# CPU.net
KiCad netlist of a schematic drawn in Altium Designer
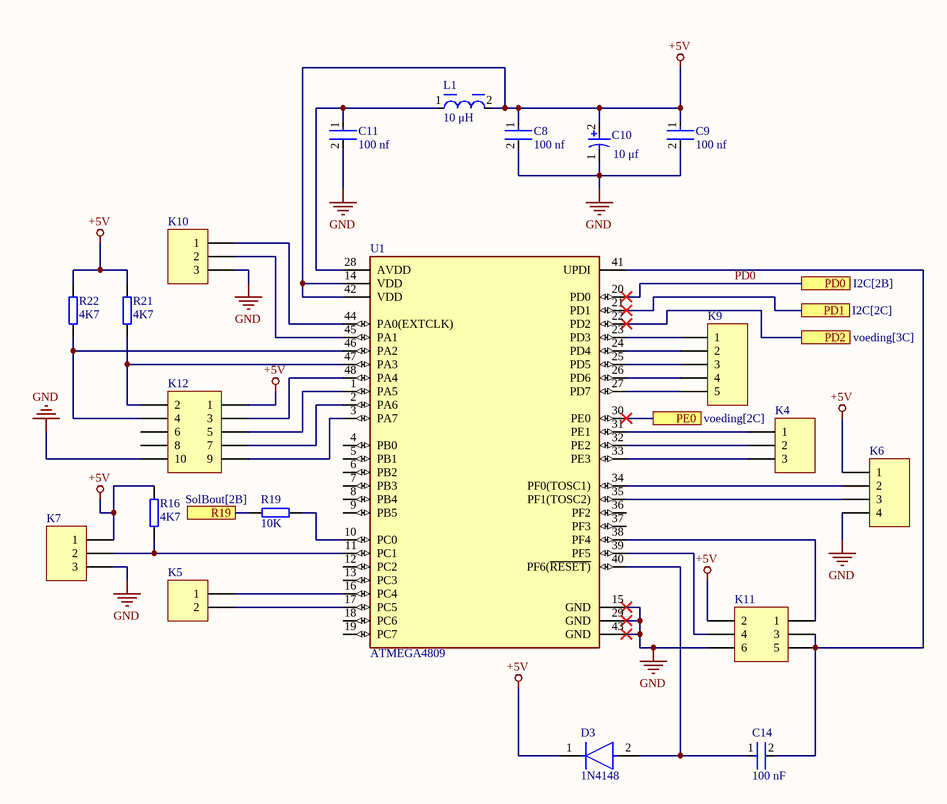
[diagram p0: CPU.SchDoc]

(export (version "E")
  (design (tool "Eeschema 10.0.6"))
  (components
    (comp (ref "C8")
      (value "100 nf")
      (footprint "CC_0805_L")
      (fields
        (field (name "MANUFACTURER") "KEMET")
        (field (name "OCTOPART") "https://octopart.com/c0805c224k5ractu-kemet-144670")
        (field (name "MANUFACTURER PART NUMBER") "C0805C224K5RACTU")
      )
      (libsource (lib "Soldeerstation_Final") (part "Capacitor_Ceramic"))
    )
    (comp (ref "C9")
      (value "100 nf")
      (footprint "CC_0805_L")
      (fields
        (field (name "MANUFACTURER") "KEMET")
        (field (name "OCTOPART") "https://octopart.com/c0805c224k5ractu-kemet-144670")
        (field (name "MANUFACTURER PART NUMBER") "C0805C224K5RACTU")
      )
      (libsource (lib "Soldeerstation_Final") (part "Capacitor_Ceramic"))
    )
    (comp (ref "C10")
      (value "10 μf")
      (footprint "CE_D8_L10")
      (fields (field (name "MANUFACTURER") "Panasonic"))
      (libsource (lib "Soldeerstation_Final") (part "Capacitor_Electrolytic"))
    )
    (comp (ref "C11")
      (value "100 nf")
      (footprint "CC_0805_L")
      (fields
        (field (name "MANUFACTURER") "KEMET")
        (field (name "OCTOPART") "https://octopart.com/c0805c224k5ractu-kemet-144670")
        (field (name "MANUFACTURER PART NUMBER") "C0805C224K5RACTU")
      )
      (libsource (lib "Soldeerstation_Final") (part "Capacitor_Ceramic"))
    )
    (comp (ref "C14")
      (value "100 nF")
      (footprint "CC_0805_L")
      (fields
        (field (name "MANUFACTURER") "KEMET")
        (field (name "OCTOPART") "https://octopart.com/c0805c224k5ractu-kemet-144670")
        (field (name "MANUFACTURER PART NUMBER") "C0805C224K5RACTU")
      )
      (libsource (lib "Soldeerstation_Final") (part "Capacitor_Ceramic"))
    )
    (comp (ref "D3")
      (value "1N4148")
      (footprint "SOD-123FL")
      (fields
        (field (name "MANUFACTURER PART NUMBER") "1N4007")
        (field (name "MANUFACTURER") "Diotec")
        (field (name "OCTOPART") "https://octopart.com/1n4007-diotec-4040411")
      )
      (libsource (lib "Soldeerstation_Final") (part "Diode"))
    )
    (comp (ref "K4")
      (value "~")
      (footprint "HDR1X3")
      (description "Header, 3-Pin")
      (fields (field (name "PUBLISHER") "Altium Limited"))
      (libsource (lib "") (part "Header 3_1"))
    )
    (comp (ref "K5")
      (value "~")
      (footprint "HDR1X2")
      (description "Header, 2-Pin")
      (fields (field (name "PUBLISHER") "Altium Limited"))
      (libsource (lib "Miscellaneous Connectors") (part "Header 2"))
    )
    (comp (ref "K6")
      (value "~")
      (footprint "HDR1X4")
      (description "Header, 4-Pin")
      (fields (field (name "PUBLISHER") "Altium Limited"))
      (libsource (lib "Miscellaneous Connectors") (part "Header 4"))
    )
    (comp (ref "K7")
      (value "~")
      (footprint "HDR1X3")
      (description "Header, 3-Pin")
      (fields (field (name "PUBLISHER") "Altium Limited"))
      (libsource (lib "Miscellaneous Connectors") (part "Header 3"))
    )
    (comp (ref "K9")
      (value "~")
      (footprint "HDR1X5")
      (description "Header, 5-Pin")
      (fields (field (name "PUBLISHER") "Altium Limited"))
      (libsource (lib "Miscellaneous Connectors") (part "Header 5"))
    )
    (comp (ref "K10")
      (value "~")
      (footprint "HDR1X3")
      (description "Header, 3-Pin")
      (fields (field (name "PUBLISHER") "Altium Limited"))
      (libsource (lib "Miscellaneous Connectors") (part "Header 3"))
    )
    (comp (ref "K11")
      (value "~")
      (footprint "HDR2X3")
      (description "Header, 3-Pin, Dual row")
      (fields (field (name "PUBLISHER") "Altium Limited"))
      (libsource (lib "Miscellaneous Connectors") (part "Header 3X2"))
    )
    (comp (ref "K12")
      (value "~")
      (footprint "HDR2X5")
      (description "Header, 5-Pin, Dual row")
      (fields (field (name "PUBLISHER") "Altium Limited"))
      (libsource (lib "Miscellaneous Connectors") (part "Header 5X2"))
    )
    (comp (ref "L1")
      (value "10 μH")
      (footprint "CC_0805_L")
      (fields (field (name "TOLERANCE") "20%"))
      (libsource (lib "Soldeerstation_Final") (part "Choke"))
    )
    (comp (ref "R16")
      (value "4K7")
      (footprint "CC_0805_m")
      (fields (field (name "MANUFACTURER") "Vishay Dale") (field (name "PART NUMBER") "CRCW08050000Z0EA"))
      (libsource (lib "Soldeerstation_Final") (part "Resistor"))
    )
    (comp (ref "R19")
      (value "10K")
      (footprint "CC_0805_m")
      (fields (field (name "MANUFACTURER") "Vishay Dale") (field (name "PART NUMBER") "CRCW08050000Z0EA"))
      (libsource (lib "Soldeerstation_Final") (part "Resistor"))
    )
    (comp (ref "R21")
      (value "4K7")
      (footprint "CC_0805_m")
      (fields (field (name "MANUFACTURER") "Vishay Dale") (field (name "PART NUMBER") "CRCW08050000Z0EA"))
      (libsource (lib "Soldeerstation_Final") (part "Resistor"))
    )
    (comp (ref "R22")
      (value "4K7")
      (footprint "CC_0805_m")
      (fields (field (name "MANUFACTURER") "Vishay Dale") (field (name "PART NUMBER") "CRCW08050000Z0EA"))
      (libsource (lib "Soldeerstation_Final") (part "Resistor"))
    )
    (comp (ref "U1")
      (value "ATMEGA4809")
      (footprint "TQFP_48_M")
      (libsource (lib "Soldeerstation_Final") (part "ATMEGA4809"))
    )
  )
  (nets
    (net (code "1") (name "+5V") (class "Default")
      (node (ref "C10") (pin "2") (pinfunction "2_2") (pintype "passive"))
      (node (ref "C8") (pin "1") (pinfunction "1_1") (pintype "passive"))
      (node (ref "C9") (pin "1") (pinfunction "1_1") (pintype "passive"))
      (node (ref "D3") (pin "1") (pinfunction "C_1") (pintype "passive"))
      (node (ref "K11") (pin "2") (pinfunction "2_2") (pintype "passive"))
      (node (ref "K12") (pin "1") (pinfunction "1_1") (pintype "passive"))
      (node (ref "K6") (pin "1") (pinfunction "1_1") (pintype "passive"))
      (node (ref "K7") (pin "1") (pinfunction "1_1") (pintype "passive"))
      (node (ref "L1") (pin "2") (pinfunction "2_2") (pintype "passive"))
      (node (ref "R16") (pin "2") (pinfunction "2_2") (pintype "passive"))
      (node (ref "R21") (pin "2") (pinfunction "2_2") (pintype "passive"))
      (node (ref "R22") (pin "2") (pinfunction "2_2") (pintype "passive"))
      (node (ref "U1") (pin "14") (pinfunction "VDD_14") (pintype "power_in"))
      (node (ref "U1") (pin "42") (pinfunction "VDD_42") (pintype "power_in"))
    )
    (net (code "2") (name "/PD0") (class "Default")
      (node (ref "U1") (pin "20") (pinfunction "PD0_20") (pintype "bidirectional+no_connect"))
    )
    (net (code "3") (name "/PD1") (class "Default")
      (node (ref "U1") (pin "21") (pinfunction "PD1_21") (pintype "bidirectional+no_connect"))
    )
    (net (code "4") (name "/PD2") (class "Default")
      (node (ref "U1") (pin "22") (pinfunction "PD2_22") (pintype "bidirectional+no_connect"))
    )
    (net (code "5") (name "/PE0") (class "Default")
      (node (ref "U1") (pin "30") (pinfunction "PE0_30") (pintype "bidirectional+no_connect"))
    )
    (net (code "6") (name "/R19") (class "Default")
      (node (ref "R19") (pin "1") (pinfunction "1_1") (pintype "passive"))
    )
    (net (code "7") (name "GND") (class "Default")
      (node (ref "C10") (pin "1") (pinfunction "1_1") (pintype "passive"))
      (node (ref "C11") (pin "2") (pinfunction "2_2") (pintype "passive"))
      (node (ref "C8") (pin "2") (pinfunction "2_2") (pintype "passive"))
      (node (ref "C9") (pin "2") (pinfunction "2_2") (pintype "passive"))
      (node (ref "K10") (pin "3") (pinfunction "3_3") (pintype "passive"))
      (node (ref "K11") (pin "6") (pinfunction "6_6") (pintype "passive"))
      (node (ref "K12") (pin "10") (pinfunction "10_10") (pintype "passive"))
      (node (ref "K6") (pin "4") (pinfunction "4_4") (pintype "passive"))
      (node (ref "K7") (pin "3") (pinfunction "3_3") (pintype "passive"))
      (node (ref "U1") (pin "15") (pinfunction "GND_15") (pintype "open_emitter"))
      (node (ref "U1") (pin "29") (pinfunction "GND_29") (pintype "power_in"))
      (node (ref "U1") (pin "43") (pinfunction "GND_43") (pintype "power_in"))
    )
    (net (code "8") (name "Net-(D3-A)") (class "Default")
      (node (ref "C14") (pin "1") (pinfunction "1_1") (pintype "passive"))
      (node (ref "D3") (pin "2") (pinfunction "A_2") (pintype "passive"))
      (node (ref "U1") (pin "40") (pinfunction "PF6(~{RESET)}_40") (pintype "bidirectional"))
    )
    (net (code "9") (name "Net-(U1-AVDD)") (class "Default")
      (node (ref "C11") (pin "1") (pinfunction "1_1") (pintype "passive"))
      (node (ref "L1") (pin "1") (pinfunction "1_1") (pintype "passive"))
      (node (ref "U1") (pin "28") (pinfunction "AVDD_28") (pintype "power_in"))
    )
    (net (code "10") (name "Net-(U1-PA0(EXTCLK))") (class "Default")
      (node (ref "K10") (pin "1") (pinfunction "1_1") (pintype "passive"))
      (node (ref "U1") (pin "44") (pinfunction "PA0(EXTCLK)_44") (pintype "bidirectional"))
    )
    (net (code "11") (name "Net-(U1-PA1)") (class "Default")
      (node (ref "K10") (pin "2") (pinfunction "2_2") (pintype "passive"))
      (node (ref "U1") (pin "45") (pinfunction "PA1_45") (pintype "bidirectional"))
    )
    (net (code "12") (name "Net-(U1-PA2)") (class "Default")
      (node (ref "K12") (pin "4") (pinfunction "4_4") (pintype "passive"))
      (node (ref "R22") (pin "1") (pinfunction "1_1") (pintype "passive"))
      (node (ref "U1") (pin "46") (pinfunction "PA2_46") (pintype "bidirectional"))
    )
    (net (code "13") (name "Net-(U1-PA3)") (class "Default")
      (node (ref "K12") (pin "2") (pinfunction "2_2") (pintype "passive"))
      (node (ref "R21") (pin "1") (pinfunction "1_1") (pintype "passive"))
      (node (ref "U1") (pin "47") (pinfunction "PA3_47") (pintype "bidirectional"))
    )
    (net (code "14") (name "Net-(U1-PA4)") (class "Default")
      (node (ref "K12") (pin "3") (pinfunction "3_3") (pintype "passive"))
      (node (ref "U1") (pin "48") (pinfunction "PA4_48") (pintype "bidirectional"))
    )
    (net (code "15") (name "Net-(U1-PA5)") (class "Default")
      (node (ref "K12") (pin "5") (pinfunction "5_5") (pintype "passive"))
      (node (ref "U1") (pin "1") (pinfunction "PA5_1") (pintype "bidirectional"))
    )
    (net (code "16") (name "Net-(U1-PA6)") (class "Default")
      (node (ref "K12") (pin "7") (pinfunction "7_7") (pintype "passive"))
      (node (ref "U1") (pin "2") (pinfunction "PA6_2") (pintype "bidirectional"))
    )
    (net (code "17") (name "Net-(U1-PA7)") (class "Default")
      (node (ref "K12") (pin "9") (pinfunction "9_9") (pintype "passive"))
      (node (ref "U1") (pin "3") (pinfunction "PA7_3") (pintype "bidirectional"))
    )
    (net (code "18") (name "Net-(U1-PC0)") (class "Default")
      (node (ref "R19") (pin "2") (pinfunction "2_2") (pintype "passive"))
      (node (ref "U1") (pin "10") (pinfunction "PC0_10") (pintype "bidirectional"))
    )
    (net (code "19") (name "Net-(U1-PC1)") (class "Default")
      (node (ref "K7") (pin "2") (pinfunction "2_2") (pintype "passive"))
      (node (ref "R16") (pin "1") (pinfunction "1_1") (pintype "passive"))
      (node (ref "U1") (pin "11") (pinfunction "PC1_11") (pintype "bidirectional"))
    )
    (net (code "20") (name "Net-(U1-PC4)") (class "Default")
      (node (ref "K5") (pin "1") (pinfunction "1_1") (pintype "passive"))
      (node (ref "U1") (pin "16") (pinfunction "PC4_16") (pintype "bidirectional"))
    )
    (net (code "21") (name "Net-(U1-PC5)") (class "Default")
      (node (ref "K5") (pin "2") (pinfunction "2_2") (pintype "passive"))
      (node (ref "U1") (pin "17") (pinfunction "PC5_17") (pintype "bidirectional"))
    )
    (net (code "22") (name "Net-(U1-PD3)") (class "Default")
      (node (ref "K9") (pin "1") (pinfunction "1_1") (pintype "passive"))
      (node (ref "U1") (pin "23") (pinfunction "PD3_23") (pintype "bidirectional"))
    )
    (net (code "23") (name "Net-(U1-PD4)") (class "Default")
      (node (ref "K9") (pin "2") (pinfunction "2_2") (pintype "passive"))
      (node (ref "U1") (pin "24") (pinfunction "PD4_24") (pintype "bidirectional"))
    )
    (net (code "24") (name "Net-(U1-PD5)") (class "Default")
      (node (ref "K9") (pin "3") (pinfunction "3_3") (pintype "passive"))
      (node (ref "U1") (pin "25") (pinfunction "PD5_25") (pintype "bidirectional"))
    )
    (net (code "25") (name "Net-(U1-PD6)") (class "Default")
      (node (ref "K9") (pin "4") (pinfunction "4_4") (pintype "passive"))
      (node (ref "U1") (pin "26") (pinfunction "PD6_26") (pintype "bidirectional"))
    )
    (net (code "26") (name "Net-(U1-PD7)") (class "Default")
      (node (ref "K9") (pin "5") (pinfunction "5_5") (pintype "passive"))
      (node (ref "U1") (pin "27") (pinfunction "PD7_27") (pintype "bidirectional"))
    )
    (net (code "27") (name "Net-(U1-PE1)") (class "Default")
      (node (ref "K4") (pin "1") (pinfunction "1_1") (pintype "passive"))
      (node (ref "U1") (pin "31") (pinfunction "PE1_31") (pintype "bidirectional"))
    )
    (net (code "28") (name "Net-(U1-PE2)") (class "Default")
      (node (ref "K4") (pin "2") (pinfunction "2_2") (pintype "passive"))
      (node (ref "U1") (pin "32") (pinfunction "PE2_32") (pintype "bidirectional"))
    )
    (net (code "29") (name "Net-(U1-PE3)") (class "Default")
      (node (ref "K4") (pin "3") (pinfunction "3_3") (pintype "passive"))
      (node (ref "U1") (pin "33") (pinfunction "PE3_33") (pintype "bidirectional"))
    )
    (net (code "30") (name "Net-(U1-PF0(TOSC1))") (class "Default")
      (node (ref "K6") (pin "2") (pinfunction "2_2") (pintype "passive"))
      (node (ref "U1") (pin "34") (pinfunction "PF0(TOSC1)_34") (pintype "bidirectional"))
    )
    (net (code "31") (name "Net-(U1-PF1(TOSC2))") (class "Default")
      (node (ref "K6") (pin "3") (pinfunction "3_3") (pintype "passive"))
      (node (ref "U1") (pin "35") (pinfunction "PF1(TOSC2)_35") (pintype "bidirectional"))
    )
    (net (code "32") (name "Net-(U1-PF4)") (class "Default")
      (node (ref "K11") (pin "1") (pinfunction "1_1") (pintype "passive"))
      (node (ref "U1") (pin "38") (pinfunction "PF4_38") (pintype "bidirectional"))
    )
    (net (code "33") (name "Net-(U1-PF5)") (class "Default")
      (node (ref "K11") (pin "4") (pinfunction "4_4") (pintype "passive"))
      (node (ref "U1") (pin "39") (pinfunction "PF5_39") (pintype "bidirectional"))
    )
    (net (code "34") (name "Net-(U1-UPDI)") (class "Default")
      (node (ref "C14") (pin "2") (pinfunction "2_2") (pintype "passive"))
      (node (ref "K11") (pin "3") (pinfunction "3_3") (pintype "passive"))
      (node (ref "K11") (pin "5") (pinfunction "5_5") (pintype "passive"))
      (node (ref "U1") (pin "41") (pinfunction "UPDI_41") (pintype "passive"))
    )
    (net (code "35") (name "unconnected-(K12-Pad6)") (class "Default")
      (node (ref "K12") (pin "6") (pinfunction "6_6") (pintype "passive"))
    )
    (net (code "36") (name "unconnected-(K12-Pad8)") (class "Default")
      (node (ref "K12") (pin "8") (pinfunction "8_8") (pintype "passive"))
    )
    (net (code "37") (name "unconnected-(U1-PB0-Pad4)") (class "Default")
      (node (ref "U1") (pin "4") (pinfunction "PB0_4") (pintype "bidirectional"))
    )
    (net (code "38") (name "unconnected-(U1-PB1-Pad5)") (class "Default")
      (node (ref "U1") (pin "5") (pinfunction "PB1_5") (pintype "bidirectional"))
    )
    (net (code "39") (name "unconnected-(U1-PB2-Pad6)") (class "Default")
      (node (ref "U1") (pin "6") (pinfunction "PB2_6") (pintype "bidirectional"))
    )
    (net (code "40") (name "unconnected-(U1-PB3-Pad7)") (class "Default")
      (node (ref "U1") (pin "7") (pinfunction "PB3_7") (pintype "bidirectional"))
    )
    (net (code "41") (name "unconnected-(U1-PB4-Pad8)") (class "Default")
      (node (ref "U1") (pin "8") (pinfunction "PB4_8") (pintype "bidirectional"))
    )
    (net (code "42") (name "unconnected-(U1-PB5-Pad9)") (class "Default")
      (node (ref "U1") (pin "9") (pinfunction "PB5_9") (pintype "bidirectional"))
    )
    (net (code "43") (name "unconnected-(U1-PC2-Pad12)") (class "Default")
      (node (ref "U1") (pin "12") (pinfunction "PC2_12") (pintype "bidirectional"))
    )
    (net (code "44") (name "unconnected-(U1-PC3-Pad13)") (class "Default")
      (node (ref "U1") (pin "13") (pinfunction "PC3_13") (pintype "bidirectional"))
    )
    (net (code "45") (name "unconnected-(U1-PC6-Pad18)") (class "Default")
      (node (ref "U1") (pin "18") (pinfunction "PC6_18") (pintype "bidirectional"))
    )
    (net (code "46") (name "unconnected-(U1-PC7-Pad19)") (class "Default")
      (node (ref "U1") (pin "19") (pinfunction "PC7_19") (pintype "bidirectional"))
    )
    (net (code "47") (name "unconnected-(U1-PF2-Pad36)") (class "Default")
      (node (ref "U1") (pin "36") (pinfunction "PF2_36") (pintype "bidirectional"))
    )
    (net (code "48") (name "unconnected-(U1-PF3-Pad37)") (class "Default")
      (node (ref "U1") (pin "37") (pinfunction "PF3_37") (pintype "bidirectional"))
    )
  )
)
